# Sound_Light_IC_evaluation_board.net
KiCad netlist of a schematic drawn in EasyEDA Pro
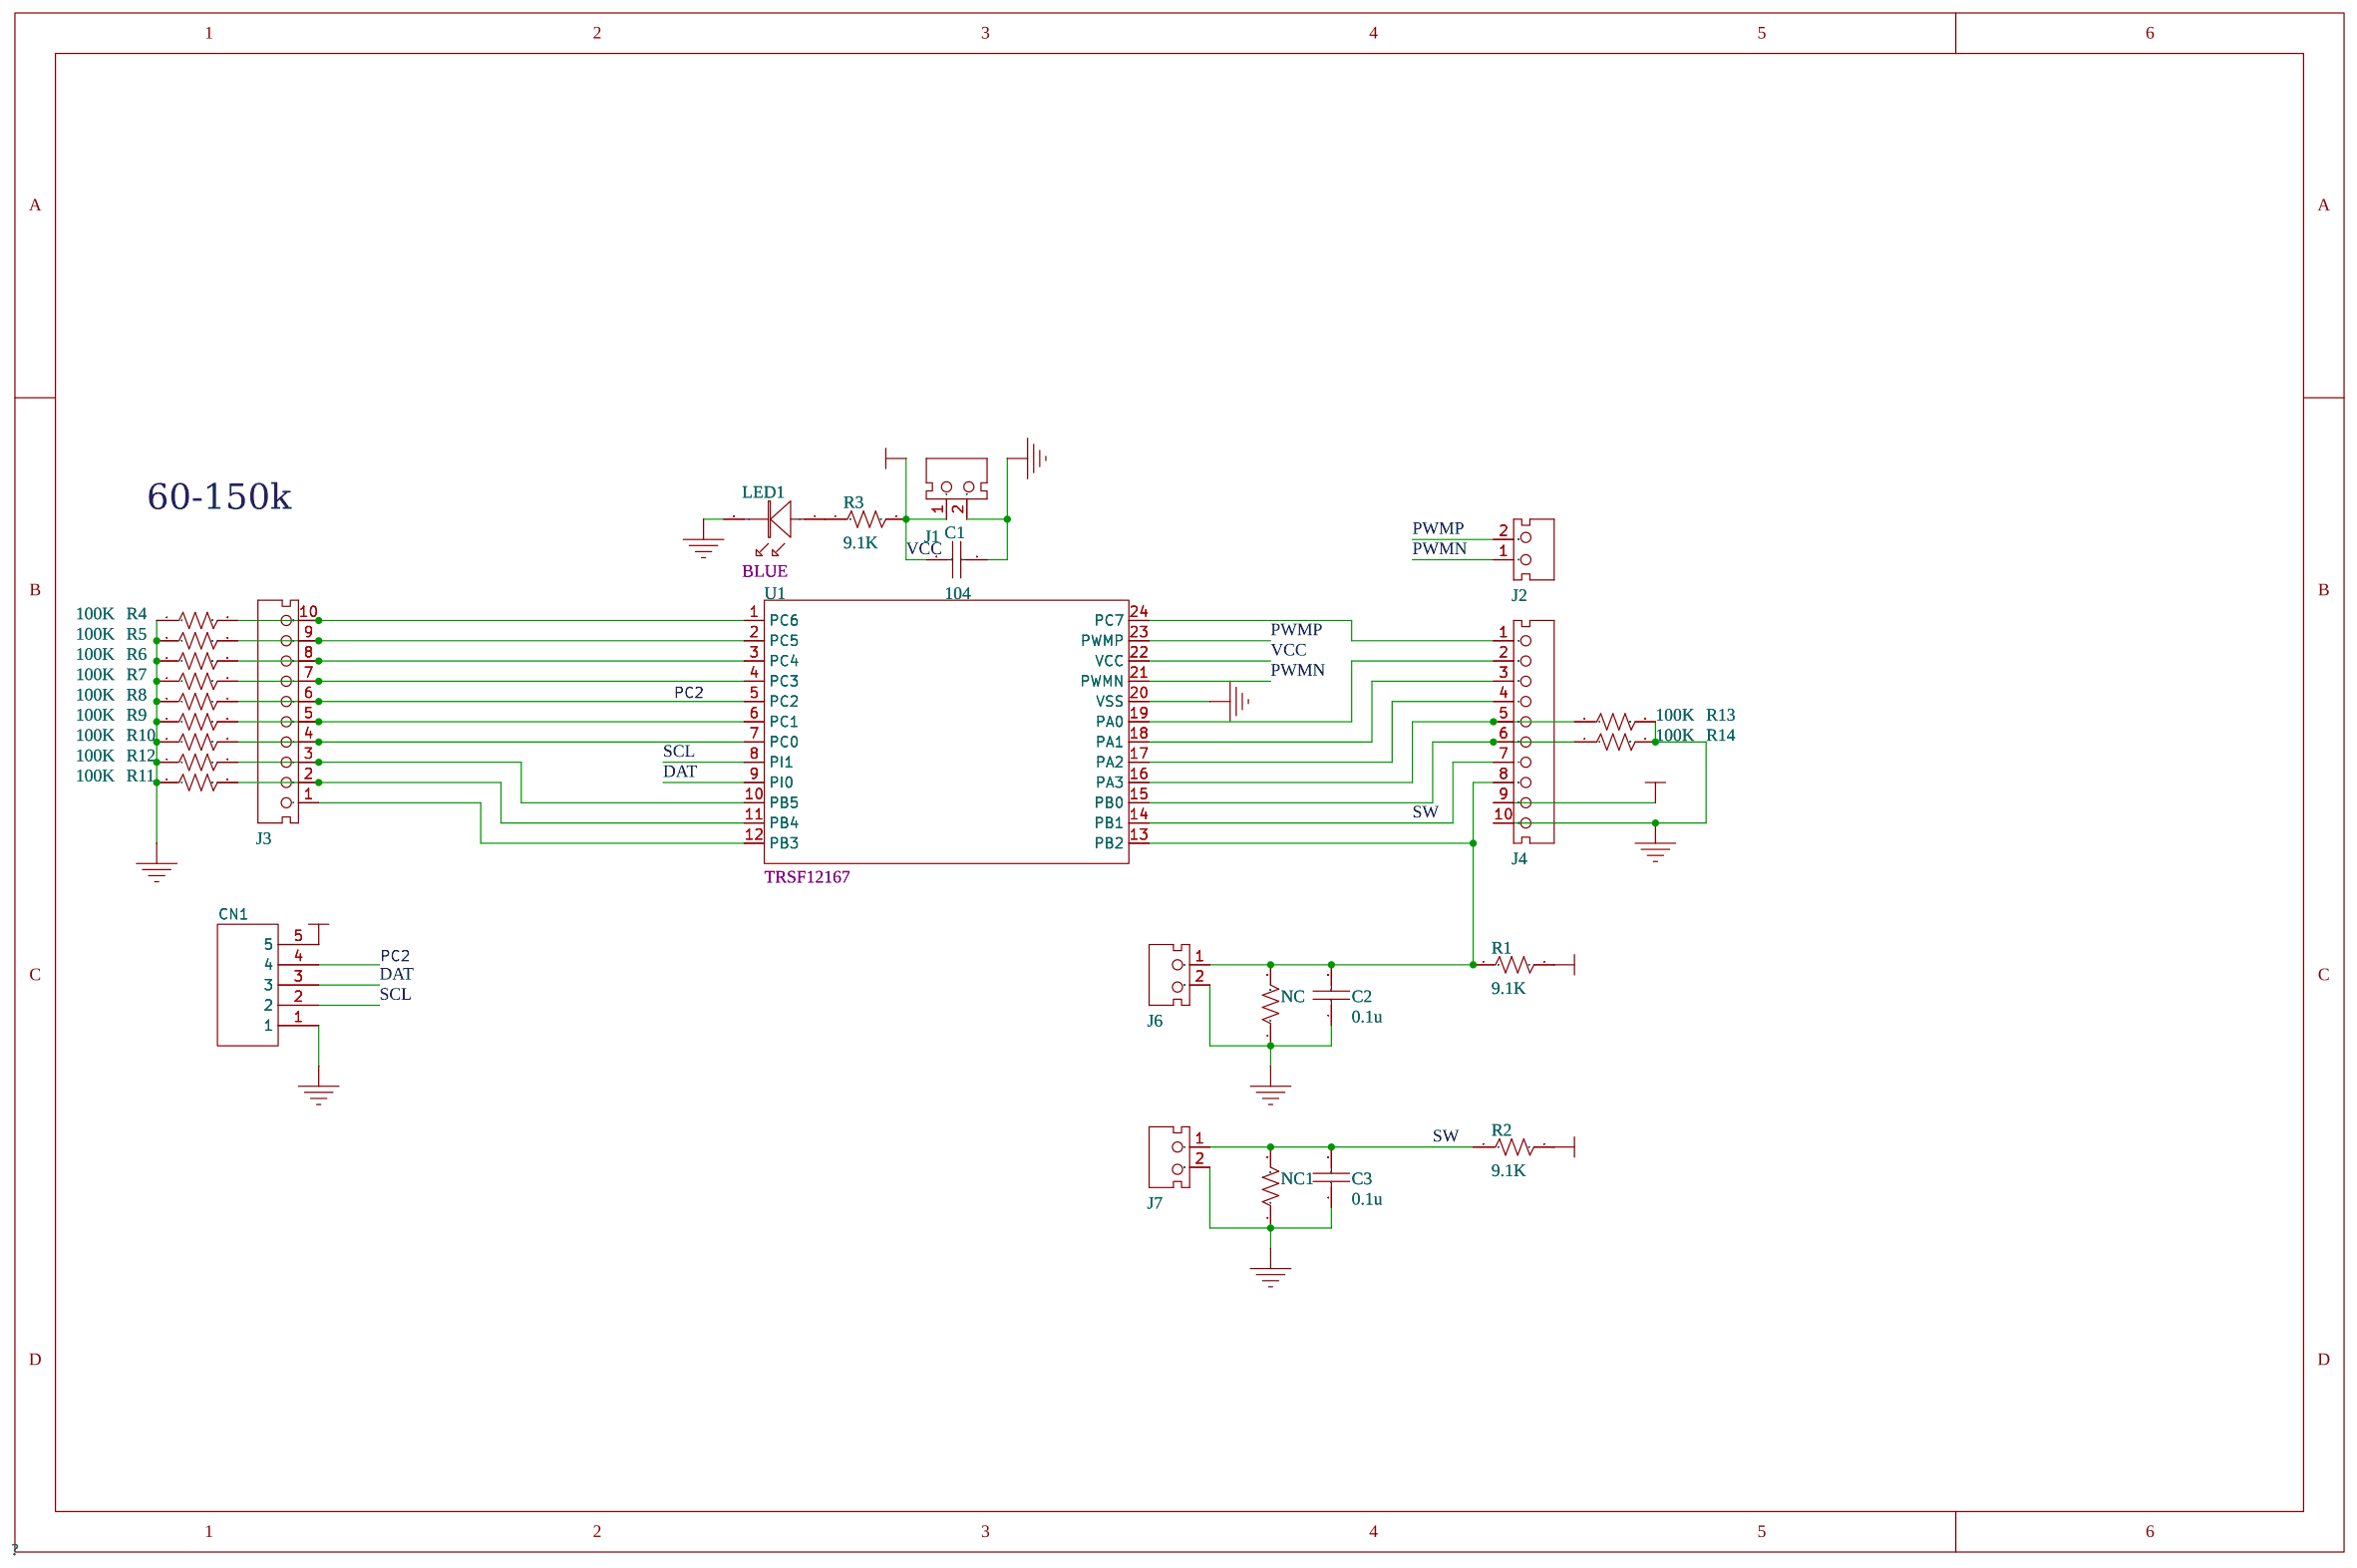
[diagram p0: schematic sheet]

(export (version "E")
  (design (tool "Eeschema 10.0.6"))
  (components
    (comp (ref "C1")
      (value "104")
      (footprint "easyedapro:CAPC0603-RW")
      (description "CAP X7R .01UF 50V +-5% 0603 WALSIN L")
      (fields
        (field (name "MFG") "WALSIN")
        (field (name "Tolerance") "5%")
        (field (name "CREATE_NAME") "Nathan")
      )
      (libsource (lib "easyedapro") (part "CAP0603 0.01uF 50V 5%_X7R_WALSIN"))
    )
    (comp (ref "C2")
      (value "0.1u")
      (footprint "easyedapro:CAPC0603-RW")
      (description "CAP X7R .01UF 50V +-5% 0603 WALSIN L")
      (fields
        (field (name "MFG") "WALSIN")
        (field (name "Tolerance") "5%")
        (field (name "CREATE_NAME") "Nathan")
      )
      (libsource (lib "easyedapro") (part "CAP0603 0.01uF 50V 5%_X7R_WALSIN"))
    )
    (comp (ref "C3")
      (value "0.1u")
      (footprint "easyedapro:CAPC0603-RW")
      (description "CAP X7R .01UF 50V +-5% 0603 WALSIN L")
      (fields
        (field (name "MFG") "WALSIN")
        (field (name "Tolerance") "5%")
        (field (name "CREATE_NAME") "Nathan")
      )
      (libsource (lib "easyedapro") (part "CAP0603 0.01uF 50V 5%_X7R_WALSIN"))
    )
    (comp (ref "CN1")
      (value "~")
      (footprint "easyedapro:CONN-TH_640456-5")
      (description "参考系列:-;间距:2.54mm;插针结构:1x5P;排数:1;每排PIN数:5;行距:-;安装方式:-;触头材质:铜合金;")
      (fields
        (field (name "Manufacturer Part") "640456-5")
        (field (name "Manufacturer") "TE Connectivity(美国泰科)")
      )
      (libsource (lib "easyedapro") (part "640456-5"))
    )
    (comp (ref "J1")
      (value "2.5mm")
      (footprint "easyedapro:CONN 2P PH=2.5mm HAA250A-2 WHITE")
      (description "CONNECTOR HA2.5 2PIN BLACK K")
      (fields
        (field (name "MFG") "金瑞康")
        (field (name "MFG Part") "HAA250A-2 BLACK")
        (field (name "CREATE_NAME") "Nathan")
      )
      (libsource (lib "easyedapro") (part "CONN 2P PH=2.5mm HAA250A-2 BLACK"))
    )
    (comp (ref "J2")
      (value "2.5mm")
      (footprint "easyedapro:CONN 2P PH=2.5mm HAA250A-2 WHITE")
      (description "CONNECTOR HA2.5 2PIN BLACK K")
      (fields
        (field (name "MFG") "金瑞康")
        (field (name "MFG Part") "HAA250A-2 BLACK")
        (field (name "CREATE_NAME") "Nathan")
      )
      (libsource (lib "easyedapro") (part "CONN 2P PH=2.5mm HAA250A-2 BLACK"))
    )
    (comp (ref "J3")
      (value "2.5mm")
      (footprint "easyedapro:CONN 10P PH=2.5mm ST CI2210P1VK0-NH")
      (description "WTB CONN. 2.5MM 10PIN CI2210P1VK0-NH CV G")
      (fields
        (field (name "MFG") "CVILUX")
        (field (name "MFG Part") "CI2210P1VK0-NH")
        (field (name "CREATE_NAME") "Nathan")
      )
      (libsource (lib "easyedapro") (part "CONN 10P PH=2.5mm ST CI2210P1VK0-NH"))
    )
    (comp (ref "J4")
      (value "2.5mm")
      (footprint "easyedapro:CONN 10P PH=2.5mm ST CI2210P1VK0-NH")
      (description "WTB CONN. 2.5MM 10PIN CI2210P1VK0-NH CV G")
      (fields
        (field (name "MFG") "CVILUX")
        (field (name "MFG Part") "CI2210P1VK0-NH")
        (field (name "CREATE_NAME") "Nathan")
      )
      (libsource (lib "easyedapro") (part "CONN 10P PH=2.5mm ST CI2210P1VK0-NH"))
    )
    (comp (ref "J6")
      (value "2.5mm")
      (footprint "easyedapro:CONN 2P PH=2.5mm HAA250A-2 WHITE")
      (description "CONNECTOR HA2.5 2PIN BLACK K")
      (fields
        (field (name "MFG") "金瑞康")
        (field (name "MFG Part") "HAA250A-2 BLACK")
        (field (name "CREATE_NAME") "Nathan")
      )
      (libsource (lib "easyedapro") (part "CONN 2P PH=2.5mm HAA250A-2 BLACK"))
    )
    (comp (ref "J7")
      (value "2.5mm")
      (footprint "easyedapro:CONN 2P PH=2.5mm HAA250A-2 WHITE")
      (description "CONNECTOR HA2.5 2PIN BLACK K")
      (fields
        (field (name "MFG") "金瑞康")
        (field (name "MFG Part") "HAA250A-2 BLACK")
        (field (name "CREATE_NAME") "Nathan")
      )
      (libsource (lib "easyedapro") (part "CONN 2P PH=2.5mm HAA250A-2 BLACK"))
    )
    (comp (ref "LED1")
      (value "T575011480204")
      (footprint "easyedapro:LED0603_BLUE")
      (description "LED 465 0603 LTST-C193TBK LITEON ( L")
      (fields
        (field (name "Color") "BLUE")
        (field (name "MFG") "LITEON (光寶)")
        (field (name "MFG Part") "LTST-C193TBKT-5A")
        (field (name "CREATE_NAME") "Nathan")
      )
      (libsource (lib "easyedapro") (part "LED0603B_LTST-C193TBKT-5A"))
    )
    (comp (ref "NC")
      (value "9.1K")
      (footprint "easyedapro:0603-RW")
      (description "CHIP 29.4K OHM 100PPM +-1% 0603 WALS L")
      (fields
        (field (name "MFG") "WALSIN")
        (field (name "MFG Part") "WR06X2942FTL")
        (field (name "CREATE_NAME") "Tom")
      )
      (libsource (lib "easyedapro") (part "RES0603 1/10W +-0.1% 29.4K OHM 100PPM"))
    )
    (comp (ref "NC1")
      (value "9.1K")
      (footprint "easyedapro:0603-RW")
      (description "CHIP 29.4K OHM 100PPM +-1% 0603 WALS L")
      (fields
        (field (name "MFG") "WALSIN")
        (field (name "MFG Part") "WR06X2942FTL")
        (field (name "CREATE_NAME") "Tom")
      )
      (libsource (lib "easyedapro") (part "RES0603 1/10W +-0.1% 29.4K OHM 100PPM"))
    )
    (comp (ref "R1")
      (value "9.1K")
      (footprint "easyedapro:0603-RW")
      (description "CHIP 29.4K OHM 100PPM +-1% 0603 WALS L")
      (fields
        (field (name "MFG") "WALSIN")
        (field (name "MFG Part") "WR06X2942FTL")
        (field (name "CREATE_NAME") "Tom")
      )
      (libsource (lib "easyedapro") (part "RES0603 1/10W +-0.1% 29.4K OHM 100PPM"))
    )
    (comp (ref "R2")
      (value "9.1K")
      (footprint "easyedapro:0603-RW")
      (description "CHIP 29.4K OHM 100PPM +-1% 0603 WALS L")
      (fields
        (field (name "MFG") "WALSIN")
        (field (name "MFG Part") "WR06X2942FTL")
        (field (name "CREATE_NAME") "Tom")
      )
      (libsource (lib "easyedapro") (part "RES0603 1/10W +-0.1% 29.4K OHM 100PPM"))
    )
    (comp (ref "R3")
      (value "9.1K")
      (footprint "easyedapro:0603-RW")
      (description "CHIP 29.4K OHM 100PPM +-1% 0603 WALS L")
      (fields
        (field (name "MFG") "WALSIN")
        (field (name "MFG Part") "WR06X2942FTL")
        (field (name "CREATE_NAME") "Tom")
      )
      (libsource (lib "easyedapro") (part "RES0603 1/10W +-0.1% 29.4K OHM 100PPM"))
    )
    (comp (ref "R4")
      (value "100K")
      (footprint "easyedapro:0603-RW")
      (description "CHIP 29.4K OHM 100PPM +-1% 0603 WALS L")
      (fields
        (field (name "MFG") "WALSIN")
        (field (name "MFG Part") "WR06X2942FTL")
        (field (name "CREATE_NAME") "Tom")
      )
      (libsource (lib "easyedapro") (part "RES0603 1/10W +-0.1% 29.4K OHM 100PPM"))
    )
    (comp (ref "R5")
      (value "100K")
      (footprint "easyedapro:0603-RW")
      (description "CHIP 29.4K OHM 100PPM +-1% 0603 WALS L")
      (fields
        (field (name "MFG") "WALSIN")
        (field (name "MFG Part") "WR06X2942FTL")
        (field (name "CREATE_NAME") "Tom")
      )
      (libsource (lib "easyedapro") (part "RES0603 1/10W +-0.1% 29.4K OHM 100PPM"))
    )
    (comp (ref "R6")
      (value "100K")
      (footprint "easyedapro:0603-RW")
      (description "CHIP 29.4K OHM 100PPM +-1% 0603 WALS L")
      (fields
        (field (name "MFG") "WALSIN")
        (field (name "MFG Part") "WR06X2942FTL")
        (field (name "CREATE_NAME") "Tom")
      )
      (libsource (lib "easyedapro") (part "RES0603 1/10W +-0.1% 29.4K OHM 100PPM"))
    )
    (comp (ref "R7")
      (value "100K")
      (footprint "easyedapro:0603-RW")
      (description "CHIP 29.4K OHM 100PPM +-1% 0603 WALS L")
      (fields
        (field (name "MFG") "WALSIN")
        (field (name "MFG Part") "WR06X2942FTL")
        (field (name "CREATE_NAME") "Tom")
      )
      (libsource (lib "easyedapro") (part "RES0603 1/10W +-0.1% 29.4K OHM 100PPM"))
    )
    (comp (ref "R8")
      (value "100K")
      (footprint "easyedapro:0603-RW")
      (description "CHIP 29.4K OHM 100PPM +-1% 0603 WALS L")
      (fields
        (field (name "MFG") "WALSIN")
        (field (name "MFG Part") "WR06X2942FTL")
        (field (name "CREATE_NAME") "Tom")
      )
      (libsource (lib "easyedapro") (part "RES0603 1/10W +-0.1% 29.4K OHM 100PPM"))
    )
    (comp (ref "R9")
      (value "100K")
      (footprint "easyedapro:0603-RW")
      (description "CHIP 29.4K OHM 100PPM +-1% 0603 WALS L")
      (fields
        (field (name "MFG") "WALSIN")
        (field (name "MFG Part") "WR06X2942FTL")
        (field (name "CREATE_NAME") "Tom")
      )
      (libsource (lib "easyedapro") (part "RES0603 1/10W +-0.1% 29.4K OHM 100PPM"))
    )
    (comp (ref "R10")
      (value "100K")
      (footprint "easyedapro:0603-RW")
      (description "CHIP 29.4K OHM 100PPM +-1% 0603 WALS L")
      (fields
        (field (name "MFG") "WALSIN")
        (field (name "MFG Part") "WR06X2942FTL")
        (field (name "CREATE_NAME") "Tom")
      )
      (libsource (lib "easyedapro") (part "RES0603 1/10W +-0.1% 29.4K OHM 100PPM"))
    )
    (comp (ref "R11")
      (value "100K")
      (footprint "easyedapro:0603-RW")
      (description "CHIP 29.4K OHM 100PPM +-1% 0603 WALS L")
      (fields
        (field (name "MFG") "WALSIN")
        (field (name "MFG Part") "WR06X2942FTL")
        (field (name "CREATE_NAME") "Tom")
      )
      (libsource (lib "easyedapro") (part "RES0603 1/10W +-0.1% 29.4K OHM 100PPM"))
    )
    (comp (ref "R12")
      (value "100K")
      (footprint "easyedapro:0603-RW")
      (description "CHIP 29.4K OHM 100PPM +-1% 0603 WALS L")
      (fields
        (field (name "MFG") "WALSIN")
        (field (name "MFG Part") "WR06X2942FTL")
        (field (name "CREATE_NAME") "Tom")
      )
      (libsource (lib "easyedapro") (part "RES0603 1/10W +-0.1% 29.4K OHM 100PPM"))
    )
    (comp (ref "R13")
      (value "100K")
      (footprint "easyedapro:0603-RW")
      (description "CHIP 29.4K OHM 100PPM +-1% 0603 WALS L")
      (fields
        (field (name "MFG") "WALSIN")
        (field (name "MFG Part") "WR06X2942FTL")
        (field (name "CREATE_NAME") "Tom")
      )
      (libsource (lib "easyedapro") (part "RES0603 1/10W +-0.1% 29.4K OHM 100PPM"))
    )
    (comp (ref "R14")
      (value "100K")
      (footprint "easyedapro:0603-RW")
      (description "CHIP 29.4K OHM 100PPM +-1% 0603 WALS L")
      (fields
        (field (name "MFG") "WALSIN")
        (field (name "MFG Part") "WR06X2942FTL")
        (field (name "CREATE_NAME") "Tom")
      )
      (libsource (lib "easyedapro") (part "RES0603 1/10W +-0.1% 29.4K OHM 100PPM"))
    )
    (comp (ref "U1")
      (value "BS86C08C 24SSOP")
      (footprint "easyedapro:SSOP24(150mil)")
      (description "BS86C08C_24SSOP")
      (fields
        (field (name "MFG") "HOLTEK")
        (field (name "MFG Part") "TRSF12167")
        (field (name "CREATE_NAME") "Nathan")
      )
      (libsource (lib "easyedapro") (part "BS86C08C 24SSOP"))
    )
  )
  (nets
    (net (code "1") (name "/DAT") (class "Default")
      (node (ref "CN1") (pin "3") (pinfunction "3_3") (pintype "input"))
      (node (ref "U1") (pin "9") (pinfunction "PI0_9") (pintype "input"))
    )
    (net (code "2") (name "/PC2") (class "Default")
      (node (ref "CN1") (pin "4") (pinfunction "4_4") (pintype "input"))
      (node (ref "J3") (pin "6") (pinfunction "6_6") (pintype "input"))
      (node (ref "R8") (pin "2") (pinfunction "2_2") (pintype "input"))
      (node (ref "U1") (pin "5") (pinfunction "PC2_5") (pintype "input"))
    )
    (net (code "3") (name "/PWMN") (class "Default")
      (node (ref "J2") (pin "1") (pinfunction "1_1") (pintype "input"))
      (node (ref "U1") (pin "21") (pinfunction "PWMN_21") (pintype "input"))
    )
    (net (code "4") (name "/PWMP") (class "Default")
      (node (ref "J2") (pin "2") (pinfunction "2_2") (pintype "input"))
      (node (ref "U1") (pin "23") (pinfunction "PWMP_23") (pintype "input"))
    )
    (net (code "5") (name "/SCL") (class "Default")
      (node (ref "CN1") (pin "2") (pinfunction "2_2") (pintype "input"))
      (node (ref "U1") (pin "8") (pinfunction "PI1_8") (pintype "input"))
    )
    (net (code "6") (name "/SW") (class "Default")
      (node (ref "C3") (pin "2") (pinfunction "2_2") (pintype "input"))
      (node (ref "J4") (pin "7") (pinfunction "7_7") (pintype "input"))
      (node (ref "J7") (pin "1") (pinfunction "1_1") (pintype "input"))
      (node (ref "NC1") (pin "2") (pinfunction "2_2") (pintype "input"))
      (node (ref "R2") (pin "1") (pinfunction "1_1") (pintype "input"))
      (node (ref "U1") (pin "14") (pinfunction "PB1_14") (pintype "input"))
    )
    (net (code "7") (name "GND") (class "Default")
      (node (ref "C1") (pin "1") (pinfunction "1_1") (pintype "input"))
      (node (ref "C2") (pin "1") (pinfunction "1_1") (pintype "input"))
      (node (ref "C3") (pin "1") (pinfunction "1_1") (pintype "input"))
      (node (ref "CN1") (pin "1") (pinfunction "1_1") (pintype "input"))
      (node (ref "J1") (pin "2") (pinfunction "2_2") (pintype "input"))
      (node (ref "J4") (pin "10") (pinfunction "10_10") (pintype "input"))
      (node (ref "J6") (pin "2") (pinfunction "2_2") (pintype "input"))
      (node (ref "J7") (pin "2") (pinfunction "2_2") (pintype "input"))
      (node (ref "LED1") (pin "2") (pinfunction "K_2") (pintype "input"))
      (node (ref "NC") (pin "1") (pinfunction "1_1") (pintype "input"))
      (node (ref "NC1") (pin "1") (pinfunction "1_1") (pintype "input"))
      (node (ref "R10") (pin "1") (pinfunction "1_1") (pintype "input"))
      (node (ref "R11") (pin "1") (pinfunction "1_1") (pintype "input"))
      (node (ref "R12") (pin "1") (pinfunction "1_1") (pintype "input"))
      (node (ref "R13") (pin "2") (pinfunction "2_2") (pintype "input"))
      (node (ref "R14") (pin "2") (pinfunction "2_2") (pintype "input"))
      (node (ref "R4") (pin "1") (pinfunction "1_1") (pintype "input"))
      (node (ref "R5") (pin "1") (pinfunction "1_1") (pintype "input"))
      (node (ref "R6") (pin "1") (pinfunction "1_1") (pintype "input"))
      (node (ref "R7") (pin "1") (pinfunction "1_1") (pintype "input"))
      (node (ref "R8") (pin "1") (pinfunction "1_1") (pintype "input"))
      (node (ref "R9") (pin "1") (pinfunction "1_1") (pintype "input"))
      (node (ref "U1") (pin "20") (pinfunction "VSS_20") (pintype "input"))
    )
    (net (code "8") (name "Net-(LED1-A)") (class "Default")
      (node (ref "LED1") (pin "1") (pinfunction "A_1") (pintype "input"))
      (node (ref "R3") (pin "1") (pinfunction "1_1") (pintype "input"))
    )
    (net (code "9") (name "Net-(U1-PA0)") (class "Default")
      (node (ref "J4") (pin "2") (pinfunction "2_2") (pintype "input"))
      (node (ref "U1") (pin "19") (pinfunction "PA0_19") (pintype "input"))
    )
    (net (code "10") (name "Net-(U1-PA1)") (class "Default")
      (node (ref "J4") (pin "3") (pinfunction "3_3") (pintype "input"))
      (node (ref "U1") (pin "18") (pinfunction "PA1_18") (pintype "input"))
    )
    (net (code "11") (name "Net-(U1-PA2)") (class "Default")
      (node (ref "J4") (pin "4") (pinfunction "4_4") (pintype "input"))
      (node (ref "U1") (pin "17") (pinfunction "PA2_17") (pintype "input"))
    )
    (net (code "12") (name "Net-(U1-PA3)") (class "Default")
      (node (ref "J4") (pin "5") (pinfunction "5_5") (pintype "input"))
      (node (ref "R13") (pin "1") (pinfunction "1_1") (pintype "input"))
      (node (ref "U1") (pin "16") (pinfunction "PA3_16") (pintype "input"))
    )
    (net (code "13") (name "Net-(U1-PB0)") (class "Default")
      (node (ref "J4") (pin "6") (pinfunction "6_6") (pintype "input"))
      (node (ref "R14") (pin "1") (pinfunction "1_1") (pintype "input"))
      (node (ref "U1") (pin "15") (pinfunction "PB0_15") (pintype "input"))
    )
    (net (code "14") (name "Net-(U1-PB2)") (class "Default")
      (node (ref "C2") (pin "2") (pinfunction "2_2") (pintype "input"))
      (node (ref "J4") (pin "8") (pinfunction "8_8") (pintype "input"))
      (node (ref "J6") (pin "1") (pinfunction "1_1") (pintype "input"))
      (node (ref "NC") (pin "2") (pinfunction "2_2") (pintype "input"))
      (node (ref "R1") (pin "1") (pinfunction "1_1") (pintype "input"))
      (node (ref "U1") (pin "13") (pinfunction "PB2_13") (pintype "input"))
    )
    (net (code "15") (name "Net-(U1-PB3)") (class "Default")
      (node (ref "J3") (pin "1") (pinfunction "1_1") (pintype "input"))
      (node (ref "U1") (pin "12") (pinfunction "PB3_12") (pintype "input"))
    )
    (net (code "16") (name "Net-(U1-PB4)") (class "Default")
      (node (ref "J3") (pin "2") (pinfunction "2_2") (pintype "input"))
      (node (ref "R11") (pin "2") (pinfunction "2_2") (pintype "input"))
      (node (ref "U1") (pin "11") (pinfunction "PB4_11") (pintype "input"))
    )
    (net (code "17") (name "Net-(U1-PB5)") (class "Default")
      (node (ref "J3") (pin "3") (pinfunction "3_3") (pintype "input"))
      (node (ref "R12") (pin "2") (pinfunction "2_2") (pintype "input"))
      (node (ref "U1") (pin "10") (pinfunction "PB5_10") (pintype "input"))
    )
    (net (code "18") (name "Net-(U1-PC0)") (class "Default")
      (node (ref "J3") (pin "4") (pinfunction "4_4") (pintype "input"))
      (node (ref "R10") (pin "2") (pinfunction "2_2") (pintype "input"))
      (node (ref "U1") (pin "7") (pinfunction "PC0_7") (pintype "input"))
    )
    (net (code "19") (name "Net-(U1-PC1)") (class "Default")
      (node (ref "J3") (pin "5") (pinfunction "5_5") (pintype "input"))
      (node (ref "R9") (pin "2") (pinfunction "2_2") (pintype "input"))
      (node (ref "U1") (pin "6") (pinfunction "PC1_6") (pintype "input"))
    )
    (net (code "20") (name "Net-(U1-PC3)") (class "Default")
      (node (ref "J3") (pin "7") (pinfunction "7_7") (pintype "input"))
      (node (ref "R7") (pin "2") (pinfunction "2_2") (pintype "input"))
      (node (ref "U1") (pin "4") (pinfunction "PC3_4") (pintype "input"))
    )
    (net (code "21") (name "Net-(U1-PC4)") (class "Default")
      (node (ref "J3") (pin "8") (pinfunction "8_8") (pintype "input"))
      (node (ref "R6") (pin "2") (pinfunction "2_2") (pintype "input"))
      (node (ref "U1") (pin "3") (pinfunction "PC4_3") (pintype "input"))
    )
    (net (code "22") (name "Net-(U1-PC5)") (class "Default")
      (node (ref "J3") (pin "9") (pinfunction "9_9") (pintype "input"))
      (node (ref "R5") (pin "2") (pinfunction "2_2") (pintype "input"))
      (node (ref "U1") (pin "2") (pinfunction "PC5_2") (pintype "input"))
    )
    (net (code "23") (name "Net-(U1-PC6)") (class "Default")
      (node (ref "J3") (pin "10") (pinfunction "10_10") (pintype "input"))
      (node (ref "R4") (pin "2") (pinfunction "2_2") (pintype "input"))
      (node (ref "U1") (pin "1") (pinfunction "PC6_1") (pintype "input"))
    )
    (net (code "24") (name "Net-(U1-PC7)") (class "Default")
      (node (ref "J4") (pin "1") (pinfunction "1_1") (pintype "input"))
      (node (ref "U1") (pin "24") (pinfunction "PC7_24") (pintype "input"))
    )
    (net (code "25") (name "VCC") (class "Default")
      (node (ref "C1") (pin "2") (pinfunction "2_2") (pintype "input"))
      (node (ref "CN1") (pin "5") (pinfunction "5_5") (pintype "input"))
      (node (ref "J1") (pin "1") (pinfunction "1_1") (pintype "input"))
      (node (ref "J4") (pin "9") (pinfunction "9_9") (pintype "input"))
      (node (ref "R1") (pin "2") (pinfunction "2_2") (pintype "input"))
      (node (ref "R2") (pin "2") (pinfunction "2_2") (pintype "input"))
      (node (ref "R3") (pin "2") (pinfunction "2_2") (pintype "input"))
      (node (ref "U1") (pin "22") (pinfunction "VCC_22") (pintype "input"))
    )
  )
)
